# oneLab_PCB_V4.net
KiCad netlist of a schematic drawn in EAGLE
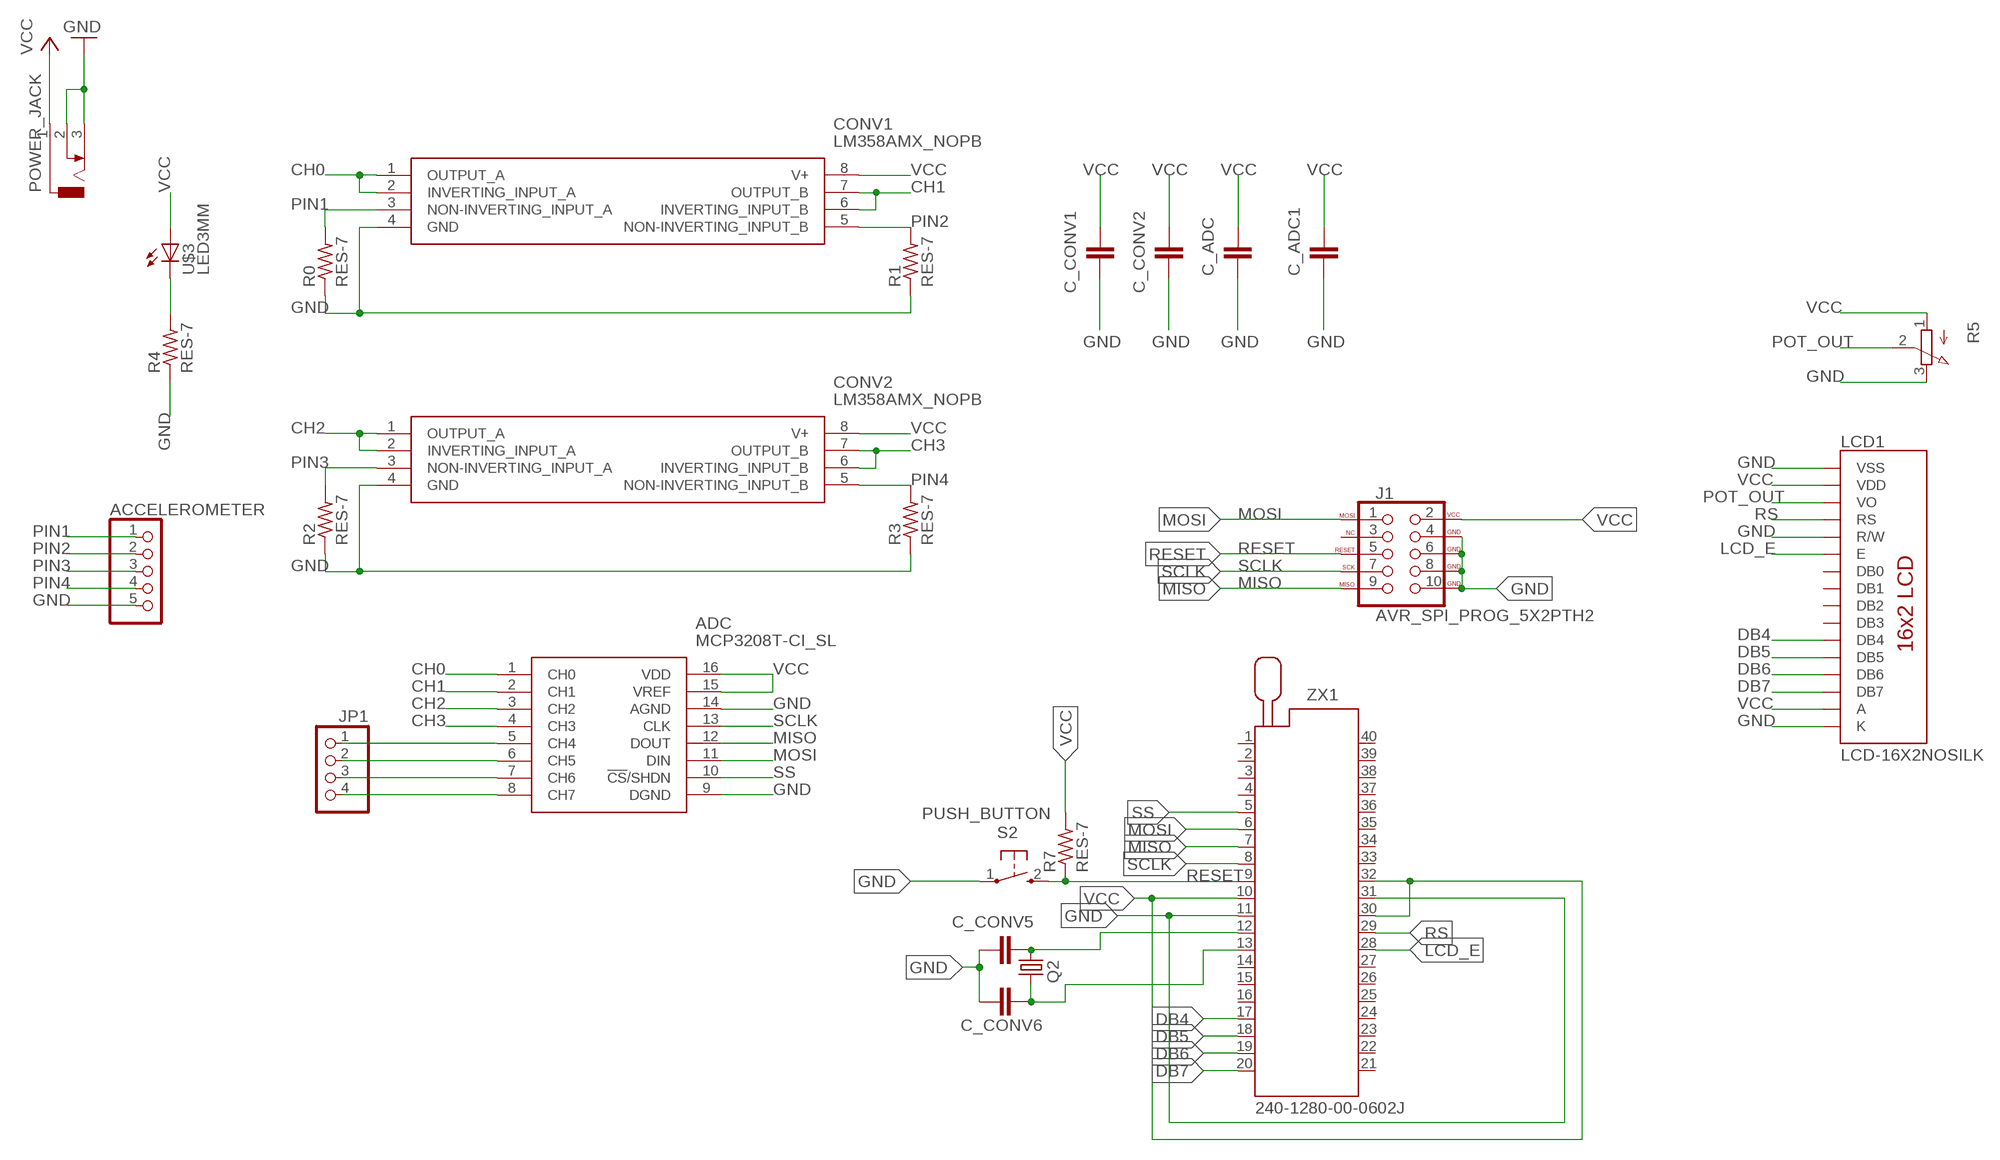
[diagram p0: schematic, sheet 1]

(export (version "E")
  (design (tool "Eeschema 10.0.6"))
  (components
    (comp (ref "ACCELEROMETER")
      (value "PINHD-5_DATA")
      (footprint "eagle-import:1X05_DATA")
      (libsource (lib "eagle-import") (part "PINHD-5_DATA"))
    )
    (comp (ref "ADC")
      (value "MCP3208T-CI_SL")
      (footprint "eagle-import:SOIC127P600X175-16N")
      (fields
        (field (name "ARROW_PART_NUMBER") "MCP3208T-CI/SL")
        (field (name "MOUSER_PART_NUMBER") "579-MCP3208T-CI/SL")
      )
      (libsource (lib "eagle-import") (part "MCP3208T-CI_SL"))
    )
    (comp (ref "CONV1")
      (value "LM358AMX_NOPB")
      (footprint "eagle-import:SOIC127P600X175-8N")
      (fields
        (field (name "ARROW_PART_NUMBER") "LM358AMX/NOPB")
        (field (name "MOUSER_PART_NUMBER") "926-LM358AMX/NOPB")
      )
      (libsource (lib "eagle-import") (part "LM358AMX_NOPB"))
    )
    (comp (ref "CONV2")
      (value "LM358AMX_NOPB")
      (footprint "eagle-import:SOIC127P600X175-8N")
      (fields
        (field (name "ARROW_PART_NUMBER") "LM358AMX/NOPB")
        (field (name "MOUSER_PART_NUMBER") "926-LM358AMX/NOPB")
      )
      (libsource (lib "eagle-import") (part "LM358AMX_NOPB"))
    )
    (comp (ref "C_ADC")
      (value "CAPACITOR")
      (footprint "eagle-import:C025-025X050")
      (libsource (lib "eagle-import") (part "CAPACITOR"))
    )
    (comp (ref "C_ADC1")
      (value "CAPACITOR")
      (footprint "eagle-import:C025-025X050")
      (libsource (lib "eagle-import") (part "CAPACITOR"))
    )
    (comp (ref "C_CONV1")
      (value "CAPACITOR")
      (footprint "eagle-import:C025-025X050")
      (libsource (lib "eagle-import") (part "CAPACITOR"))
    )
    (comp (ref "C_CONV2")
      (value "CAPACITOR")
      (footprint "eagle-import:C025-025X050")
      (libsource (lib "eagle-import") (part "CAPACITOR"))
    )
    (comp (ref "C_CONV5")
      (value "CAPACITOR")
      (footprint "eagle-import:C025-025X050")
      (libsource (lib "eagle-import") (part "CAPACITOR"))
    )
    (comp (ref "C_CONV6")
      (value "CAPACITOR")
      (footprint "eagle-import:C025-025X050")
      (libsource (lib "eagle-import") (part "CAPACITOR"))
    )
    (comp (ref "J1")
      (value "AVR_SPI_PROG_5X2PTH2")
      (footprint "eagle-import:2X5-SHROUDED")
      (libsource (lib "eagle-import") (part "AVR_SPI_PROG_5X2PTH2"))
    )
    (comp (ref "JP1")
      (value "PINHD-4_DATA")
      (footprint "eagle-import:1X04_DATA")
      (libsource (lib "eagle-import") (part "PINHD-4_DATA"))
    )
    (comp (ref "LCD1")
      (value "LCD-16X2NOSILK")
      (footprint "eagle-import:LCD-16X2_NOSILK")
      (libsource (lib "eagle-import") (part "LCD-16X2NOSILK"))
    )
    (comp (ref "POWER_JACK")
      (value "CON_JACK")
      (footprint "eagle-import:DCJ0303")
      (libsource (lib "eagle-import") (part "CON_JACK"))
    )
    (comp (ref "Q2")
      (value "CRYSTALHC49U-V")
      (footprint "eagle-import:HC49U-V")
      (libsource (lib "eagle-import") (part "CRYSTALHC49U-V"))
    )
    (comp (ref "R0")
      (value "RES-7")
      (footprint "eagle-import:0204_7")
      (libsource (lib "eagle-import") (part "RES-7"))
    )
    (comp (ref "R1")
      (value "RES-7")
      (footprint "eagle-import:0204_7")
      (libsource (lib "eagle-import") (part "RES-7"))
    )
    (comp (ref "R2")
      (value "RES-7")
      (footprint "eagle-import:0204_7")
      (libsource (lib "eagle-import") (part "RES-7"))
    )
    (comp (ref "R3")
      (value "RES-7")
      (footprint "eagle-import:0204_7")
      (libsource (lib "eagle-import") (part "RES-7"))
    )
    (comp (ref "R4")
      (value "RES-7")
      (footprint "eagle-import:0204_7")
      (libsource (lib "eagle-import") (part "RES-7"))
    )
    (comp (ref "R5")
      (value "POT")
      (footprint "eagle-import:3RP_1610N")
      (libsource (lib "eagle-import") (part "POT"))
    )
    (comp (ref "R7")
      (value "RES-7")
      (footprint "eagle-import:0204_7")
      (libsource (lib "eagle-import") (part "RES-7"))
    )
    (comp (ref "S2")
      (value "PUSH_BUTTON")
      (footprint "eagle-import:B3F-10XX")
      (libsource (lib "eagle-import") (part "PUSH_BUTTON"))
    )
    (comp (ref "U$3")
      (value "LED3MM")
      (footprint "eagle-import:LED3MM")
      (libsource (lib "eagle-import") (part "LED3MM"))
    )
    (comp (ref "ZX1")
      (value "240-1280-00-0602J")
      (footprint "eagle-import:240-1280-00-0602J")
      (libsource (lib "eagle-import") (part "240-?-00-0602J1280"))
    )
  )
  (nets
    (net (code "1") (name "/CH0") (class "Default")
      (node (ref "ADC") (pin "1") (pinfunction "CH0_1") (pintype "bidirectional"))
      (node (ref "CONV1") (pin "1") (pinfunction "OUTPUT_A_1") (pintype "bidirectional"))
      (node (ref "CONV1") (pin "2") (pinfunction "INVERTING_INPUT_A_2") (pintype "bidirectional"))
    )
    (net (code "2") (name "/CH1") (class "Default")
      (node (ref "ADC") (pin "2") (pinfunction "CH1_2") (pintype "bidirectional"))
      (node (ref "CONV1") (pin "6") (pinfunction "INVERTING_INPUT_B_6") (pintype "bidirectional"))
      (node (ref "CONV1") (pin "7") (pinfunction "OUTPUT_B_7") (pintype "bidirectional"))
    )
    (net (code "3") (name "/CH2") (class "Default")
      (node (ref "ADC") (pin "3") (pinfunction "CH2_3") (pintype "bidirectional"))
      (node (ref "CONV2") (pin "1") (pinfunction "OUTPUT_A_1") (pintype "bidirectional"))
      (node (ref "CONV2") (pin "2") (pinfunction "INVERTING_INPUT_A_2") (pintype "bidirectional"))
    )
    (net (code "4") (name "/CH3") (class "Default")
      (node (ref "ADC") (pin "4") (pinfunction "CH3_4") (pintype "bidirectional"))
      (node (ref "CONV2") (pin "6") (pinfunction "INVERTING_INPUT_B_6") (pintype "bidirectional"))
      (node (ref "CONV2") (pin "7") (pinfunction "OUTPUT_B_7") (pintype "bidirectional"))
    )
    (net (code "5") (name "/PIN1") (class "Default")
      (node (ref "ACCELEROMETER") (pin "1") (pinfunction "1_1") (pintype "passive"))
      (node (ref "CONV1") (pin "3") (pinfunction "NON-INVERTING_INPUT_A_3") (pintype "bidirectional"))
      (node (ref "R0") (pin "2") (pinfunction "2_2") (pintype "passive"))
    )
    (net (code "6") (name "/PIN2") (class "Default")
      (node (ref "ACCELEROMETER") (pin "2") (pinfunction "2_2") (pintype "passive"))
      (node (ref "CONV1") (pin "5") (pinfunction "NON-INVERTING_INPUT_B_5") (pintype "bidirectional"))
      (node (ref "R1") (pin "2") (pinfunction "2_2") (pintype "passive"))
    )
    (net (code "7") (name "/PIN3") (class "Default")
      (node (ref "ACCELEROMETER") (pin "3") (pinfunction "3_3") (pintype "passive"))
      (node (ref "CONV2") (pin "3") (pinfunction "NON-INVERTING_INPUT_A_3") (pintype "bidirectional"))
      (node (ref "R2") (pin "2") (pinfunction "2_2") (pintype "passive"))
    )
    (net (code "8") (name "/PIN4") (class "Default")
      (node (ref "ACCELEROMETER") (pin "4") (pinfunction "4_4") (pintype "passive"))
      (node (ref "CONV2") (pin "5") (pinfunction "NON-INVERTING_INPUT_B_5") (pintype "bidirectional"))
      (node (ref "R3") (pin "2") (pinfunction "2_2") (pintype "passive"))
    )
    (net (code "9") (name "/POT_OUT") (class "Default")
      (node (ref "LCD1") (pin "3") (pinfunction "VO_3") (pintype "bidirectional"))
      (node (ref "R5") (pin "2") (pinfunction "S_2") (pintype "passive"))
    )
    (net (code "10") (name "DB4") (class "Default")
      (node (ref "LCD1") (pin "11") (pinfunction "DB4_11") (pintype "bidirectional"))
      (node (ref "ZX1") (pin "17") (pinfunction "17_17") (pintype "passive"))
    )
    (net (code "11") (name "DB5") (class "Default")
      (node (ref "LCD1") (pin "12") (pinfunction "DB5_12") (pintype "bidirectional"))
      (node (ref "ZX1") (pin "18") (pinfunction "18_18") (pintype "passive"))
    )
    (net (code "12") (name "DB6") (class "Default")
      (node (ref "LCD1") (pin "13") (pinfunction "DB6_13") (pintype "bidirectional"))
      (node (ref "ZX1") (pin "19") (pinfunction "19_19") (pintype "passive"))
    )
    (net (code "13") (name "DB7") (class "Default")
      (node (ref "LCD1") (pin "14") (pinfunction "DB7_14") (pintype "bidirectional"))
      (node (ref "ZX1") (pin "20") (pinfunction "20_20") (pintype "passive"))
    )
    (net (code "14") (name "GND") (class "Default")
      (node (ref "ACCELEROMETER") (pin "5") (pinfunction "5_5") (pintype "passive"))
      (node (ref "ADC") (pin "14") (pinfunction "AGND_14") (pintype "bidirectional"))
      (node (ref "ADC") (pin "9") (pinfunction "DGND_9") (pintype "bidirectional"))
      (node (ref "CONV1") (pin "4") (pinfunction "GND_4") (pintype "bidirectional"))
      (node (ref "CONV2") (pin "4") (pinfunction "GND_4") (pintype "bidirectional"))
      (node (ref "C_ADC") (pin "2") (pinfunction "2_2") (pintype "passive"))
      (node (ref "C_ADC1") (pin "2") (pinfunction "2_2") (pintype "passive"))
      (node (ref "C_CONV1") (pin "2") (pinfunction "2_2") (pintype "passive"))
      (node (ref "C_CONV2") (pin "2") (pinfunction "2_2") (pintype "passive"))
      (node (ref "C_CONV5") (pin "1") (pinfunction "1_1") (pintype "passive"))
      (node (ref "C_CONV6") (pin "1") (pinfunction "1_1") (pintype "passive"))
      (node (ref "J1") (pin "10") (pinfunction "GND_10") (pintype "power_in"))
      (node (ref "J1") (pin "4") (pinfunction "GND_4") (pintype "power_in"))
      (node (ref "J1") (pin "6") (pinfunction "GND_6") (pintype "power_in"))
      (node (ref "J1") (pin "8") (pinfunction "GND_8") (pintype "power_in"))
      (node (ref "LCD1") (pin "1") (pinfunction "VSS_1") (pintype "power_in"))
      (node (ref "LCD1") (pin "16") (pinfunction "K_16") (pintype "power_in"))
      (node (ref "LCD1") (pin "5") (pinfunction "R/W_5") (pintype "input"))
      (node (ref "POWER_JACK") (pin "2") (pinfunction "2_2") (pintype "passive"))
      (node (ref "POWER_JACK") (pin "3") (pinfunction "3_3") (pintype "passive"))
      (node (ref "R0") (pin "1") (pinfunction "1_1") (pintype "passive"))
      (node (ref "R1") (pin "1") (pinfunction "1_1") (pintype "passive"))
      (node (ref "R2") (pin "1") (pinfunction "1_1") (pintype "passive"))
      (node (ref "R3") (pin "1") (pinfunction "1_1") (pintype "passive"))
      (node (ref "R4") (pin "1") (pinfunction "1_1") (pintype "passive"))
      (node (ref "R5") (pin "3") (pinfunction "E_3") (pintype "passive"))
      (node (ref "S2") (pin "1") (pinfunction "P_1") (pintype "passive"))
      (node (ref "ZX1") (pin "11") (pinfunction "11_11") (pintype "passive"))
      (node (ref "ZX1") (pin "31") (pinfunction "31_31") (pintype "passive"))
    )
    (net (code "15") (name "LCD_E") (class "Default")
      (node (ref "LCD1") (pin "6") (pinfunction "E_6") (pintype "input"))
      (node (ref "ZX1") (pin "28") (pinfunction "28_28") (pintype "passive"))
    )
    (net (code "16") (name "MISO") (class "Default")
      (node (ref "ADC") (pin "12") (pinfunction "DOUT_12") (pintype "bidirectional"))
      (node (ref "J1") (pin "9") (pinfunction "MISO_9") (pintype "passive"))
      (node (ref "ZX1") (pin "7") (pinfunction "7_7") (pintype "passive"))
    )
    (net (code "17") (name "MOSI") (class "Default")
      (node (ref "ADC") (pin "11") (pinfunction "DIN_11") (pintype "bidirectional"))
      (node (ref "J1") (pin "1") (pinfunction "MOSI_1") (pintype "passive"))
      (node (ref "ZX1") (pin "6") (pinfunction "6_6") (pintype "passive"))
    )
    (net (code "18") (name "Net-(ADC-CH4)") (class "Default")
      (node (ref "ADC") (pin "5") (pinfunction "CH4_5") (pintype "bidirectional"))
      (node (ref "JP1") (pin "1") (pinfunction "1_1") (pintype "passive"))
    )
    (net (code "19") (name "Net-(ADC-CH5)") (class "Default")
      (node (ref "ADC") (pin "6") (pinfunction "CH5_6") (pintype "bidirectional"))
      (node (ref "JP1") (pin "2") (pinfunction "2_2") (pintype "passive"))
    )
    (net (code "20") (name "Net-(ADC-CH6)") (class "Default")
      (node (ref "ADC") (pin "7") (pinfunction "CH6_7") (pintype "bidirectional"))
      (node (ref "JP1") (pin "3") (pinfunction "3_3") (pintype "passive"))
    )
    (net (code "21") (name "Net-(ADC-CH7)") (class "Default")
      (node (ref "ADC") (pin "8") (pinfunction "CH7_8") (pintype "bidirectional"))
      (node (ref "JP1") (pin "4") (pinfunction "4_4") (pintype "passive"))
    )
    (net (code "22") (name "Net-(C_CONV5-Pad2)") (class "Default")
      (node (ref "C_CONV5") (pin "2") (pinfunction "2_2") (pintype "passive"))
      (node (ref "Q2") (pin "2") (pinfunction "2_2") (pintype "passive"))
      (node (ref "ZX1") (pin "12") (pinfunction "12_12") (pintype "passive"))
    )
    (net (code "23") (name "Net-(C_CONV6-Pad2)") (class "Default")
      (node (ref "C_CONV6") (pin "2") (pinfunction "2_2") (pintype "passive"))
      (node (ref "Q2") (pin "1") (pinfunction "1_1") (pintype "passive"))
      (node (ref "ZX1") (pin "13") (pinfunction "13_13") (pintype "passive"))
    )
    (net (code "24") (name "Net-(U$3-C)") (class "Default")
      (node (ref "R4") (pin "2") (pinfunction "2_2") (pintype "passive"))
      (node (ref "U$3") (pin "K") (pinfunction "C_K") (pintype "passive"))
    )
    (net (code "25") (name "RESET") (class "Default")
      (node (ref "J1") (pin "5") (pinfunction "RESET_5") (pintype "passive"))
      (node (ref "R7") (pin "1") (pinfunction "1_1") (pintype "passive"))
      (node (ref "S2") (pin "2") (pinfunction "S_2") (pintype "passive"))
      (node (ref "ZX1") (pin "9") (pinfunction "9_9") (pintype "passive"))
    )
    (net (code "26") (name "RS") (class "Default")
      (node (ref "LCD1") (pin "4") (pinfunction "RS_4") (pintype "input"))
      (node (ref "ZX1") (pin "29") (pinfunction "29_29") (pintype "passive"))
    )
    (net (code "27") (name "SCLK") (class "Default")
      (node (ref "ADC") (pin "13") (pinfunction "CLK_13") (pintype "bidirectional"))
      (node (ref "J1") (pin "7") (pinfunction "SCK_7") (pintype "passive"))
      (node (ref "ZX1") (pin "8") (pinfunction "8_8") (pintype "passive"))
    )
    (net (code "28") (name "SS") (class "Default")
      (node (ref "ADC") (pin "10") (pinfunction "~{CS}/SHDN_10") (pintype "bidirectional"))
      (node (ref "ZX1") (pin "5") (pinfunction "5_5") (pintype "passive"))
    )
    (net (code "29") (name "VCC") (class "Default")
      (node (ref "ADC") (pin "15") (pinfunction "VREF_15") (pintype "bidirectional"))
      (node (ref "ADC") (pin "16") (pinfunction "VDD_16") (pintype "bidirectional"))
      (node (ref "CONV1") (pin "8") (pinfunction "V+_8") (pintype "bidirectional"))
      (node (ref "CONV2") (pin "8") (pinfunction "V+_8") (pintype "bidirectional"))
      (node (ref "C_ADC") (pin "1") (pinfunction "1_1") (pintype "passive"))
      (node (ref "C_ADC1") (pin "1") (pinfunction "1_1") (pintype "passive"))
      (node (ref "C_CONV1") (pin "1") (pinfunction "1_1") (pintype "passive"))
      (node (ref "C_CONV2") (pin "1") (pinfunction "1_1") (pintype "passive"))
      (node (ref "J1") (pin "2") (pinfunction "VCC_2") (pintype "power_in"))
      (node (ref "LCD1") (pin "15") (pinfunction "A_15") (pintype "power_in"))
      (node (ref "LCD1") (pin "2") (pinfunction "VDD_2") (pintype "power_in"))
      (node (ref "POWER_JACK") (pin "1") (pinfunction "1_1") (pintype "passive"))
      (node (ref "R5") (pin "1") (pinfunction "A_1") (pintype "passive"))
      (node (ref "R7") (pin "2") (pinfunction "2_2") (pintype "passive"))
      (node (ref "U$3") (pin "A") (pinfunction "A_A") (pintype "passive"))
      (node (ref "ZX1") (pin "10") (pinfunction "10_10") (pintype "passive"))
      (node (ref "ZX1") (pin "30") (pinfunction "30_30") (pintype "passive"))
      (node (ref "ZX1") (pin "32") (pinfunction "32_32") (pintype "passive"))
    )
    (net (code "30") (name "unconnected-(J1-NC-Pad3)") (class "Default")
      (node (ref "J1") (pin "3") (pinfunction "NC_3") (pintype "no_connect"))
    )
    (net (code "31") (name "unconnected-(LCD1-DB0-Pad7)") (class "Default")
      (node (ref "LCD1") (pin "7") (pinfunction "DB0_7") (pintype "bidirectional"))
    )
    (net (code "32") (name "unconnected-(LCD1-DB1-Pad8)") (class "Default")
      (node (ref "LCD1") (pin "8") (pinfunction "DB1_8") (pintype "bidirectional"))
    )
    (net (code "33") (name "unconnected-(LCD1-DB2-Pad9)") (class "Default")
      (node (ref "LCD1") (pin "9") (pinfunction "DB2_9") (pintype "bidirectional"))
    )
    (net (code "34") (name "unconnected-(LCD1-DB3-Pad10)") (class "Default")
      (node (ref "LCD1") (pin "10") (pinfunction "DB3_10") (pintype "bidirectional"))
    )
    (net (code "35") (name "unconnected-(ZX1-Pad1)") (class "Default")
      (node (ref "ZX1") (pin "1") (pinfunction "1_1") (pintype "passive"))
    )
    (net (code "36") (name "unconnected-(ZX1-Pad2)") (class "Default")
      (node (ref "ZX1") (pin "2") (pinfunction "2_2") (pintype "passive"))
    )
    (net (code "37") (name "unconnected-(ZX1-Pad3)") (class "Default")
      (node (ref "ZX1") (pin "3") (pinfunction "3_3") (pintype "passive"))
    )
    (net (code "38") (name "unconnected-(ZX1-Pad4)") (class "Default")
      (node (ref "ZX1") (pin "4") (pinfunction "4_4") (pintype "passive"))
    )
    (net (code "39") (name "unconnected-(ZX1-Pad14)") (class "Default")
      (node (ref "ZX1") (pin "14") (pinfunction "14_14") (pintype "passive"))
    )
    (net (code "40") (name "unconnected-(ZX1-Pad15)") (class "Default")
      (node (ref "ZX1") (pin "15") (pinfunction "15_15") (pintype "passive"))
    )
    (net (code "41") (name "unconnected-(ZX1-Pad16)") (class "Default")
      (node (ref "ZX1") (pin "16") (pinfunction "16_16") (pintype "passive"))
    )
    (net (code "42") (name "unconnected-(ZX1-Pad21)") (class "Default")
      (node (ref "ZX1") (pin "21") (pinfunction "21_21") (pintype "passive"))
    )
    (net (code "43") (name "unconnected-(ZX1-Pad22)") (class "Default")
      (node (ref "ZX1") (pin "22") (pinfunction "22_22") (pintype "passive"))
    )
    (net (code "44") (name "unconnected-(ZX1-Pad23)") (class "Default")
      (node (ref "ZX1") (pin "23") (pinfunction "23_23") (pintype "passive"))
    )
    (net (code "45") (name "unconnected-(ZX1-Pad24)") (class "Default")
      (node (ref "ZX1") (pin "24") (pinfunction "24_24") (pintype "passive"))
    )
    (net (code "46") (name "unconnected-(ZX1-Pad25)") (class "Default")
      (node (ref "ZX1") (pin "25") (pinfunction "25_25") (pintype "passive"))
    )
    (net (code "47") (name "unconnected-(ZX1-Pad26)") (class "Default")
      (node (ref "ZX1") (pin "26") (pinfunction "26_26") (pintype "passive"))
    )
    (net (code "48") (name "unconnected-(ZX1-Pad27)") (class "Default")
      (node (ref "ZX1") (pin "27") (pinfunction "27_27") (pintype "passive"))
    )
    (net (code "49") (name "unconnected-(ZX1-Pad33)") (class "Default")
      (node (ref "ZX1") (pin "33") (pinfunction "33_33") (pintype "passive"))
    )
    (net (code "50") (name "unconnected-(ZX1-Pad34)") (class "Default")
      (node (ref "ZX1") (pin "34") (pinfunction "34_34") (pintype "passive"))
    )
    (net (code "51") (name "unconnected-(ZX1-Pad35)") (class "Default")
      (node (ref "ZX1") (pin "35") (pinfunction "35_35") (pintype "passive"))
    )
    (net (code "52") (name "unconnected-(ZX1-Pad36)") (class "Default")
      (node (ref "ZX1") (pin "36") (pinfunction "36_36") (pintype "passive"))
    )
    (net (code "53") (name "unconnected-(ZX1-Pad37)") (class "Default")
      (node (ref "ZX1") (pin "37") (pinfunction "37_37") (pintype "passive"))
    )
    (net (code "54") (name "unconnected-(ZX1-Pad38)") (class "Default")
      (node (ref "ZX1") (pin "38") (pinfunction "38_38") (pintype "passive"))
    )
    (net (code "55") (name "unconnected-(ZX1-Pad39)") (class "Default")
      (node (ref "ZX1") (pin "39") (pinfunction "39_39") (pintype "passive"))
    )
    (net (code "56") (name "unconnected-(ZX1-Pad40)") (class "Default")
      (node (ref "ZX1") (pin "40") (pinfunction "40_40") (pintype "passive"))
    )
  )
)
